# SCH_Workshop-components_2025-10-19.net
KiCad netlist of a schematic drawn in EasyEDA
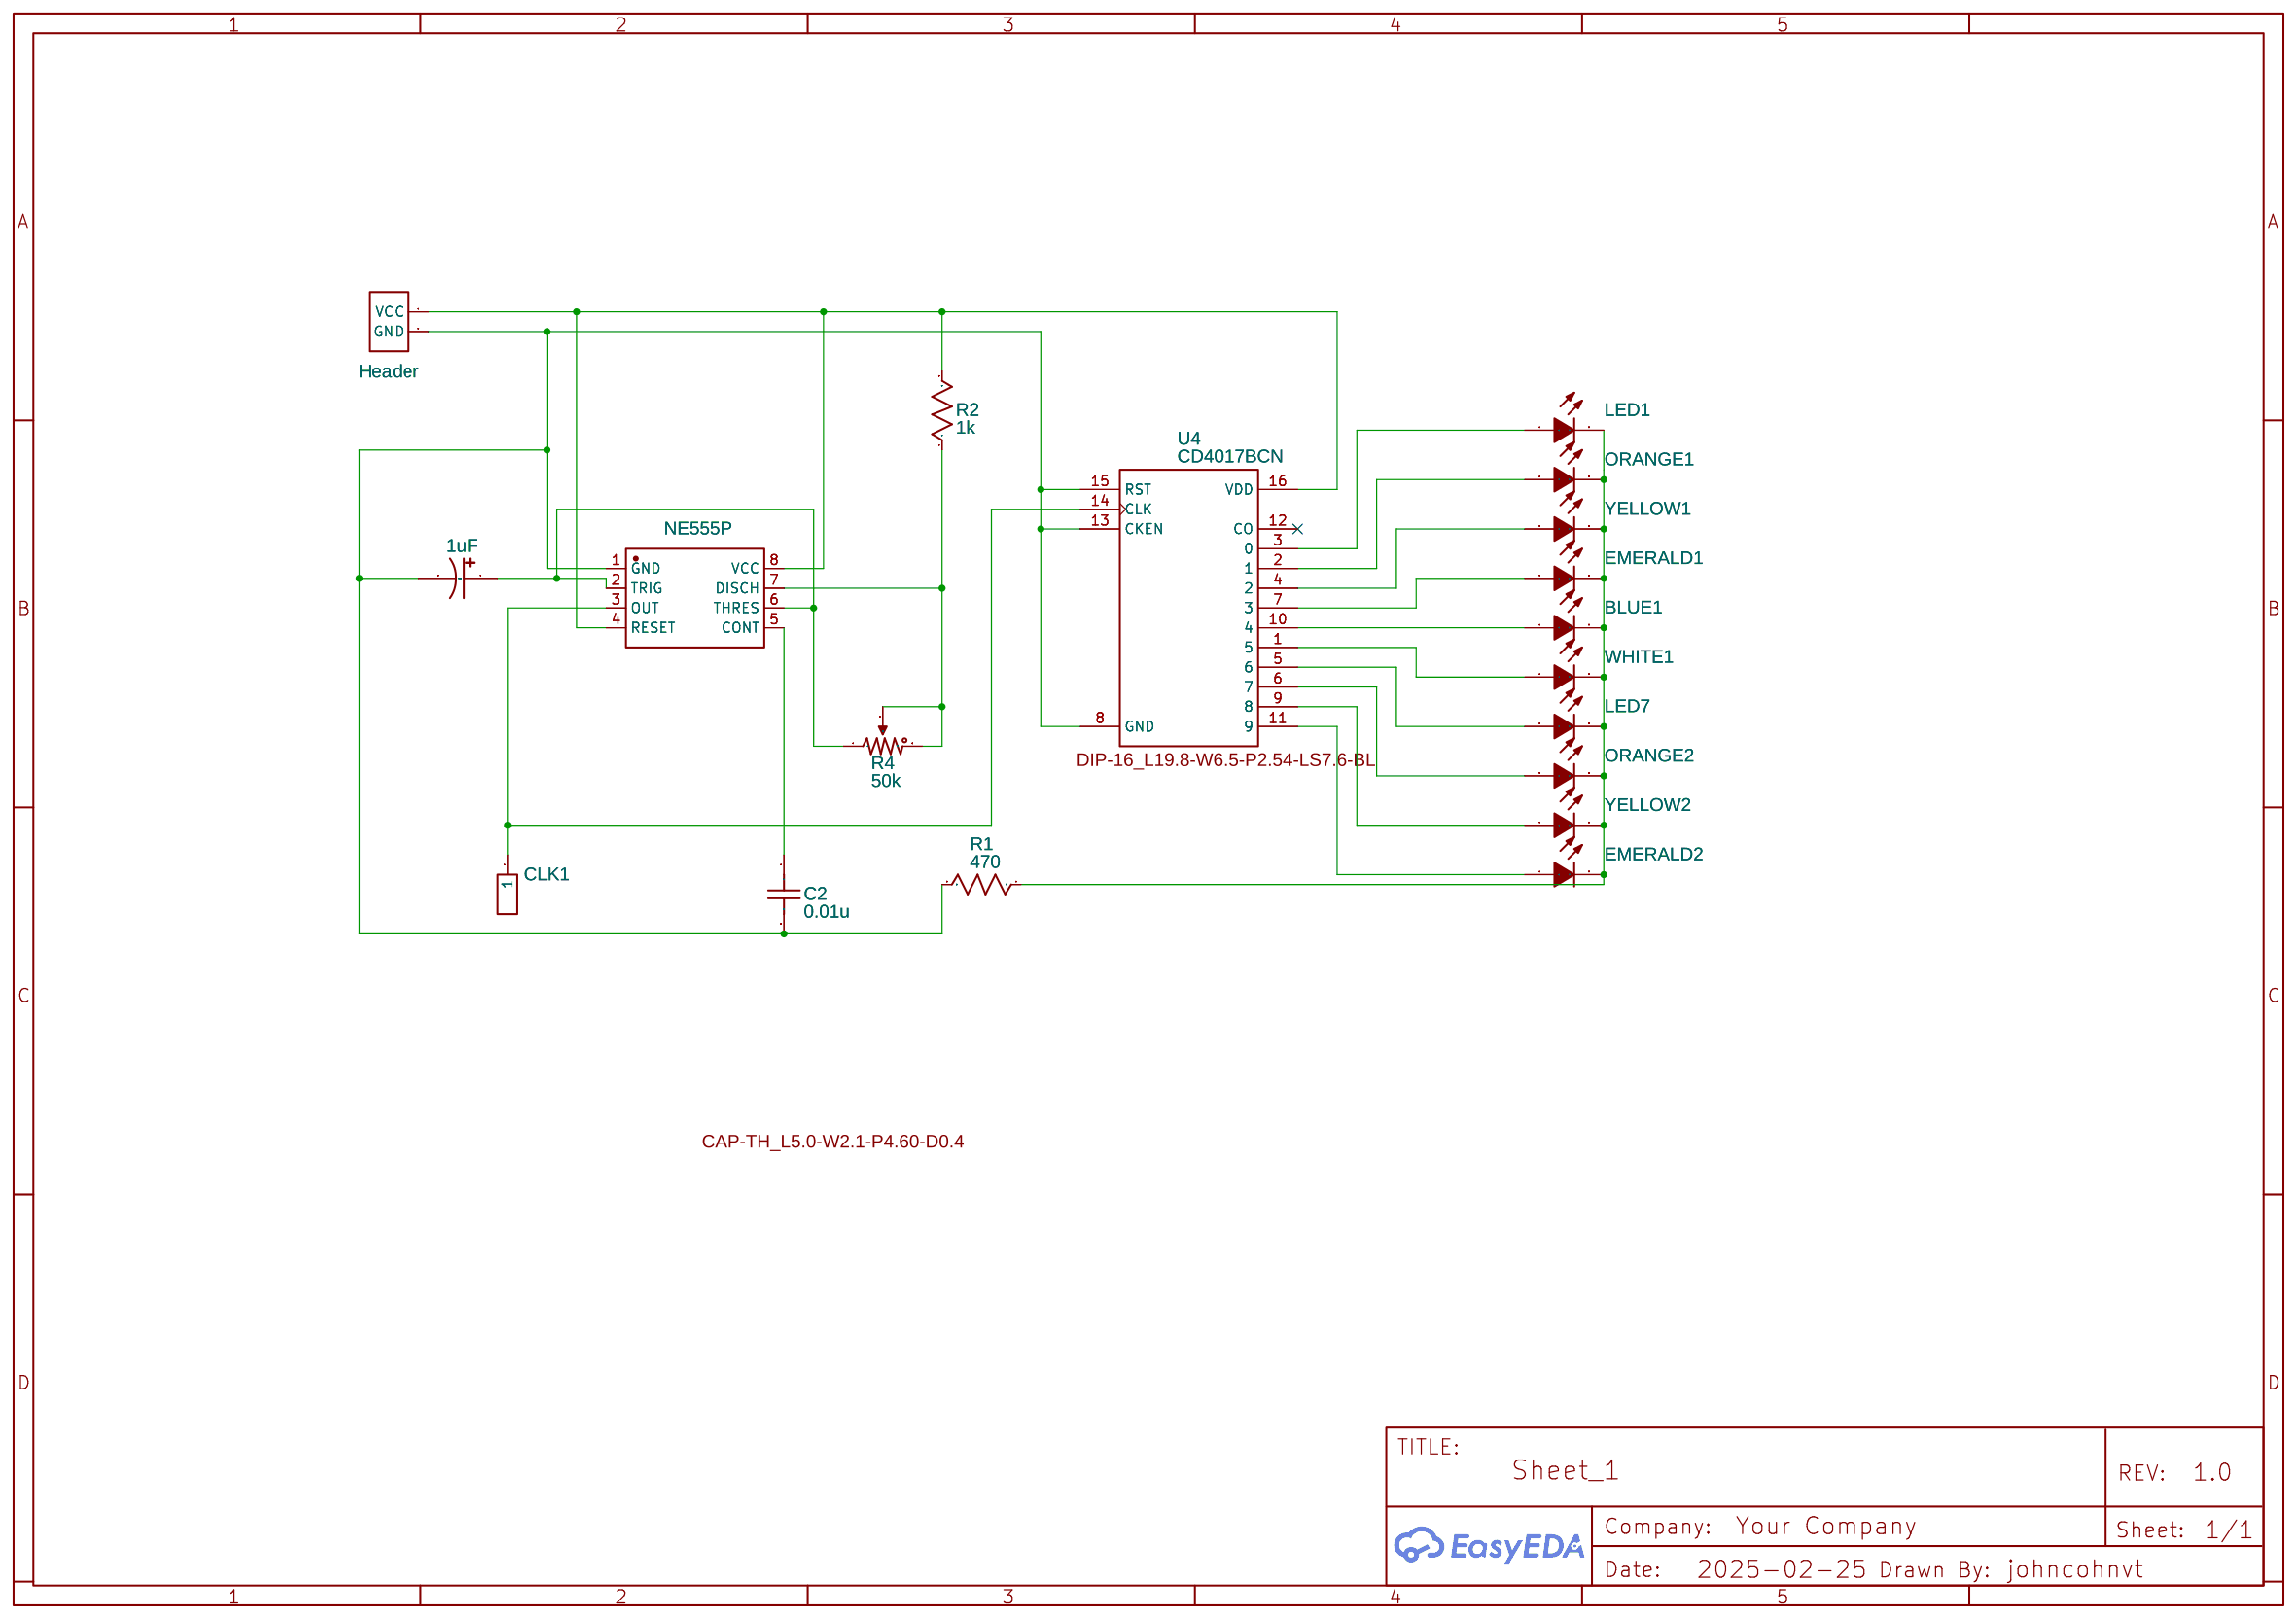
[diagram p0: schematic sheet]

(export (version "E")
  (design (tool "Eeschema 10.0.6"))
  (components
    (comp (ref "BLUE1") (value "LED_5MM") (libsource (lib "") (part "LED_5MM_4")))
    (comp (ref "C1")
      (value "1uF")
      (fields (field (name "Manufacturer Part") "UVZ1H010MDD") (field (name "Manufacturer") "Nichicon(尼吉康)"))
      (libsource (lib "") (part "UVZ1H010MDD"))
    )
    (comp (ref "C2") (value "0.01u") (libsource (lib "") (part "C_0603_US")))
    (comp (ref "CLK1")
      (value "C81276")
      (fields
        (field (name "Manufacturer Part") "2.54-1*1P针")
        (field (name "Manufacturer") "BOOMELE(Boom Precision Elec)")
      )
      (libsource (lib "") (part "Header-Male-2.54_1x1"))
    )
    (comp (ref "EMERALD1") (value "LED_5MM") (libsource (lib "") (part "LED_5MM_1")))
    (comp (ref "EMERALD2") (value "LED_5MM") (libsource (lib "") (part "LED_5MM_1")))
    (comp (ref "H1") (value "Header") (libsource (lib "") (part "HEADER-FEMALE-2.54_1X2")))
    (comp (ref "LED1") (value "LED_5MM") (libsource (lib "") (part "LED_5MM")))
    (comp (ref "LED7") (value "LED_5MM") (libsource (lib "") (part "LED_5MM")))
    (comp (ref "ORANGE1") (value "LED_5MM") (libsource (lib "") (part "LED_5MM_3")))
    (comp (ref "ORANGE2") (value "LED_5MM") (libsource (lib "") (part "LED_5MM_3")))
    (comp (ref "R1")
      (value "470")
      (fields (field (name "Manufacturer Part") "?"))
      (libsource (lib "") (part "Resistor"))
    )
    (comp (ref "R2")
      (value "1k")
      (fields (field (name "Manufacturer Part") "?"))
      (libsource (lib "") (part "Resistor_1"))
    )
    (comp (ref "R4")
      (value "50k")
      (fields (field (name "Manufacturer Part") "?"))
      (libsource (lib "") (part "Potentiometer"))
    )
    (comp (ref "U2")
      (value "NE555P")
      (fields (field (name "Manufacturer") "TI(德州仪器)"))
      (libsource (lib "") (part "NE555P"))
    )
    (comp (ref "U4") (value "CD4017BCN") (libsource (lib "") (part "CD4017BCN")))
    (comp (ref "WHITE1") (value "LED_5MM") (libsource (lib "") (part "LED_5MM_5")))
    (comp (ref "YELLOW1") (value "LED_5MM") (libsource (lib "") (part "LED_5MM_2")))
    (comp (ref "YELLOW2") (value "LED_5MM") (libsource (lib "") (part "LED_5MM_2")))
  )
  (nets
    (net (code "1") (name "Net-(BLUE1-A)") (class "Default")
      (node (ref "BLUE1") (pin "1") (pinfunction "A_1") (pintype "input"))
      (node (ref "U4") (pin "10") (pinfunction "4_10") (pintype "output"))
    )
    (net (code "2") (name "Net-(BLUE1-K)") (class "Default")
      (node (ref "BLUE1") (pin "2") (pinfunction "K_2") (pintype "input"))
      (node (ref "EMERALD1") (pin "2") (pinfunction "K_2") (pintype "input"))
      (node (ref "EMERALD2") (pin "2") (pinfunction "K_2") (pintype "input"))
      (node (ref "LED1") (pin "2") (pinfunction "K_2") (pintype "input"))
      (node (ref "LED7") (pin "2") (pinfunction "K_2") (pintype "input"))
      (node (ref "ORANGE1") (pin "2") (pinfunction "K_2") (pintype "input"))
      (node (ref "ORANGE2") (pin "2") (pinfunction "K_2") (pintype "input"))
      (node (ref "R1") (pin "1") (pinfunction "1_1") (pintype "unspecified"))
      (node (ref "WHITE1") (pin "2") (pinfunction "K_2") (pintype "input"))
      (node (ref "YELLOW1") (pin "2") (pinfunction "K_2") (pintype "input"))
      (node (ref "YELLOW2") (pin "2") (pinfunction "K_2") (pintype "input"))
    )
    (net (code "3") (name "Net-(EMERALD1-A)") (class "Default")
      (node (ref "EMERALD1") (pin "1") (pinfunction "A_1") (pintype "input"))
      (node (ref "U4") (pin "7") (pinfunction "3_7") (pintype "output"))
    )
    (net (code "4") (name "Net-(EMERALD2-A)") (class "Default")
      (node (ref "EMERALD2") (pin "1") (pinfunction "A_1") (pintype "input"))
      (node (ref "U4") (pin "11") (pinfunction "9_11") (pintype "output"))
    )
    (net (code "5") (name "Net-(H1-GND)") (class "Default")
      (node (ref "C1") (pin "2") (pinfunction "2_2") (pintype "unspecified"))
      (node (ref "C2") (pin "2") (pinfunction "2_2") (pintype "unspecified"))
      (node (ref "H1") (pin "2") (pinfunction "GND_2") (pintype "unspecified"))
      (node (ref "R1") (pin "2") (pinfunction "2_2") (pintype "unspecified"))
      (node (ref "U2") (pin "1") (pinfunction "GND_1") (pintype "unspecified"))
      (node (ref "U4") (pin "13") (pinfunction "CKEN_13") (pintype "unspecified"))
      (node (ref "U4") (pin "15") (pinfunction "RST_15") (pintype "unspecified"))
      (node (ref "U4") (pin "8") (pinfunction "GND_8") (pintype "passive"))
    )
    (net (code "6") (name "Net-(H1-VCC)") (class "Default")
      (node (ref "H1") (pin "1") (pinfunction "VCC_1") (pintype "unspecified"))
      (node (ref "R2") (pin "2") (pinfunction "2_2") (pintype "unspecified"))
      (node (ref "U2") (pin "4") (pinfunction "RESET_4") (pintype "unspecified"))
      (node (ref "U2") (pin "8") (pinfunction "VCC_8") (pintype "unspecified"))
      (node (ref "U4") (pin "16") (pinfunction "VDD_16") (pintype "passive"))
    )
    (net (code "7") (name "Net-(LED1-A)") (class "Default")
      (node (ref "LED1") (pin "1") (pinfunction "A_1") (pintype "input"))
      (node (ref "U4") (pin "3") (pinfunction "0_3") (pintype "output"))
    )
    (net (code "8") (name "Net-(LED7-A)") (class "Default")
      (node (ref "LED7") (pin "1") (pinfunction "A_1") (pintype "input"))
      (node (ref "U4") (pin "5") (pinfunction "6_5") (pintype "output"))
    )
    (net (code "9") (name "Net-(ORANGE1-A)") (class "Default")
      (node (ref "ORANGE1") (pin "1") (pinfunction "A_1") (pintype "input"))
      (node (ref "U4") (pin "2") (pinfunction "1_2") (pintype "output"))
    )
    (net (code "10") (name "Net-(ORANGE2-A)") (class "Default")
      (node (ref "ORANGE2") (pin "1") (pinfunction "A_1") (pintype "input"))
      (node (ref "U4") (pin "6") (pinfunction "7_6") (pintype "output"))
    )
    (net (code "11") (name "Net-(R4-2)") (class "Default")
      (node (ref "R2") (pin "1") (pinfunction "1_1") (pintype "unspecified"))
      (node (ref "R4") (pin "2") (pinfunction "3_2") (pintype "unspecified"))
      (node (ref "R4") (pin "3") (pinfunction "2_3") (pintype "unspecified"))
      (node (ref "U2") (pin "7") (pinfunction "DISCH_7") (pintype "unspecified"))
    )
    (net (code "12") (name "Net-(U2-CONT)") (class "Default")
      (node (ref "C2") (pin "1") (pinfunction "1_1") (pintype "unspecified"))
      (node (ref "U2") (pin "5") (pinfunction "CONT_5") (pintype "unspecified"))
    )
    (net (code "13") (name "Net-(U2-OUT)") (class "Default")
      (node (ref "CLK1") (pin "1") (pinfunction "1_1") (pintype "unspecified"))
      (node (ref "U2") (pin "3") (pinfunction "OUT_3") (pintype "unspecified"))
      (node (ref "U4") (pin "14") (pinfunction "CLK_14") (pintype "unspecified"))
    )
    (net (code "14") (name "Net-(U2-THRES)") (class "Default")
      (node (ref "C1") (pin "1") (pinfunction "1_1") (pintype "unspecified"))
      (node (ref "R4") (pin "1") (pinfunction "1_1") (pintype "unspecified"))
      (node (ref "U2") (pin "2") (pinfunction "TRIG_2") (pintype "unspecified"))
      (node (ref "U2") (pin "6") (pinfunction "THRES_6") (pintype "unspecified"))
    )
    (net (code "15") (name "Net-(U4-2)") (class "Default")
      (node (ref "U4") (pin "4") (pinfunction "2_4") (pintype "output"))
      (node (ref "YELLOW1") (pin "1") (pinfunction "A_1") (pintype "input"))
    )
    (net (code "16") (name "Net-(U4-5)") (class "Default")
      (node (ref "U4") (pin "1") (pinfunction "5_1") (pintype "output"))
      (node (ref "WHITE1") (pin "1") (pinfunction "A_1") (pintype "input"))
    )
    (net (code "17") (name "Net-(U4-8)") (class "Default")
      (node (ref "U4") (pin "9") (pinfunction "8_9") (pintype "output"))
      (node (ref "YELLOW2") (pin "1") (pinfunction "A_1") (pintype "input"))
    )
    (net (code "18") (name "unconnected-(U4-CO-Pad12)") (class "Default")
      (node (ref "U4") (pin "12") (pinfunction "CO_12") (pintype "output+no_connect"))
    )
  )
)
